# V4-AddOnLeer-V001.net
KiCad netlist of a schematic drawn in EAGLE
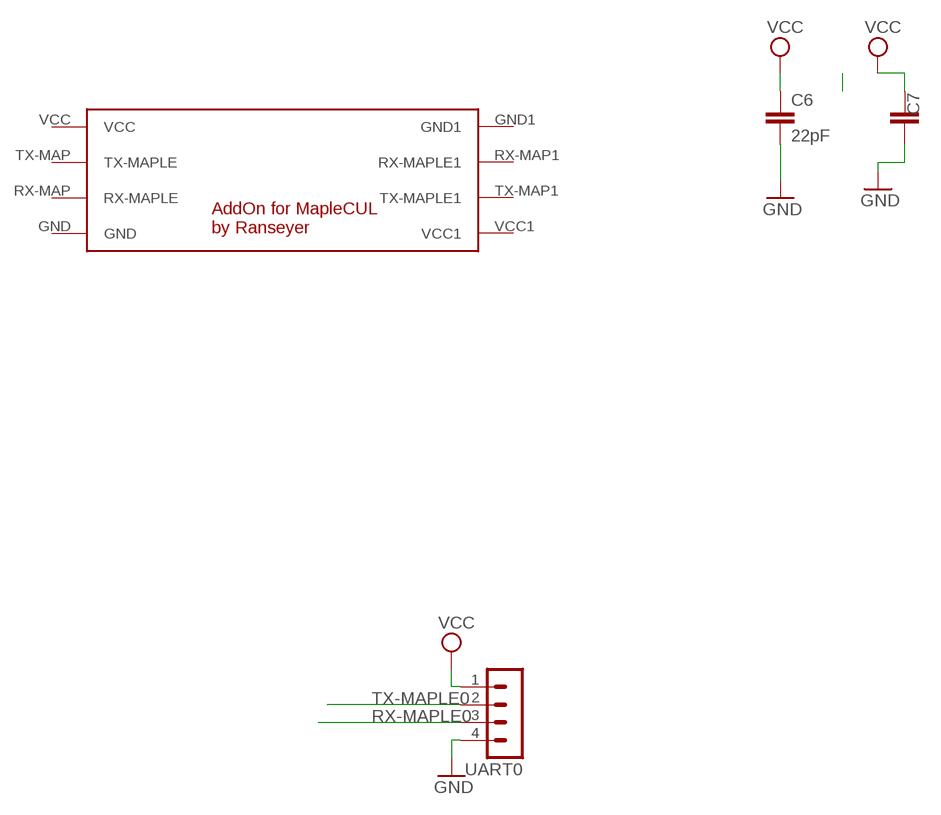
[diagram p0: schematic, sheet 1]

(export (version "E")
  (design (tool "Eeschema 10.0.6"))
  (components
    (comp (ref "C6")
      (value "22pF")
      (footprint "eagle-import:C0805")
      (libsource (lib "eagle-import") (part "C-EUC0805"))
    )
    (comp (ref "C7")
      (value "C-EUC1812")
      (footprint "eagle-import:C1812")
      (libsource (lib "eagle-import") (part "C-EUC1812"))
    )
    (comp (ref "U$1")
      (value "MAPLE-CUL-ADDON-V01")
      (footprint "eagle-import:MAPLE-CUL-V01")
      (libsource (lib "eagle-import") (part "MAPLE-CUL-ADDON-V01"))
    )
    (comp (ref "UART0")
      (value "MA04-1")
      (footprint "eagle-import:MA04-1")
      (libsource (lib "eagle-import") (part "MA04-1"))
    )
  )
  (nets
    (net (code "1") (name "/RX-MAPLE0") (class "Default")
      (node (ref "UART0") (pin "3") (pinfunction "3_3") (pintype "passive"))
    )
    (net (code "2") (name "/TX-MAPLE0") (class "Default")
      (node (ref "UART0") (pin "2") (pinfunction "2_2") (pintype "passive"))
    )
    (net (code "3") (name "GND") (class "Default")
      (node (ref "C6") (pin "2") (pinfunction "2_2") (pintype "passive"))
      (node (ref "C7") (pin "1") (pinfunction "1_1") (pintype "passive"))
      (node (ref "UART0") (pin "4") (pinfunction "4_4") (pintype "passive"))
    )
    (net (code "4") (name "VCC") (class "Default")
      (node (ref "C6") (pin "1") (pinfunction "1_1") (pintype "passive"))
      (node (ref "C7") (pin "2") (pinfunction "2_2") (pintype "passive"))
      (node (ref "UART0") (pin "1") (pinfunction "1_1") (pintype "passive"))
    )
    (net (code "5") (name "unconnected-(U$1-PadGND)") (class "Default")
      (node (ref "U$1") (pin "GND") (pinfunction "GND_GND") (pintype "bidirectional"))
    )
    (net (code "6") (name "unconnected-(U$1-PadGND1)") (class "Default")
      (node (ref "U$1") (pin "GND1") (pinfunction "GND1_GND1") (pintype "bidirectional"))
    )
    (net (code "7") (name "unconnected-(U$1-PadVCC)") (class "Default")
      (node (ref "U$1") (pin "VCC") (pinfunction "VCC_VCC") (pintype "bidirectional"))
    )
    (net (code "8") (name "unconnected-(U$1-PadVCC1)") (class "Default")
      (node (ref "U$1") (pin "VCC1") (pinfunction "VCC1_VCC1") (pintype "bidirectional"))
    )
    (net (code "9") (name "unconnected-(U$1-RX-MAPLE-PadRX-MAP)") (class "Default")
      (node (ref "U$1") (pin "RX-MAP") (pinfunction "RX-MAPLE_RX-MAP") (pintype "bidirectional"))
    )
    (net (code "10") (name "unconnected-(U$1-RX-MAPLE1-PadRX-MAP1)") (class "Default")
      (node (ref "U$1") (pin "RX-MAP1") (pinfunction "RX-MAPLE1_RX-MAP1") (pintype "bidirectional"))
    )
    (net (code "11") (name "unconnected-(U$1-TX-MAPLE-PadTX-MAP)") (class "Default")
      (node (ref "U$1") (pin "TX-MAP") (pinfunction "TX-MAPLE_TX-MAP") (pintype "bidirectional"))
    )
    (net (code "12") (name "unconnected-(U$1-TX-MAPLE1-PadTX-MAP1)") (class "Default")
      (node (ref "U$1") (pin "TX-MAP1") (pinfunction "TX-MAPLE1_TX-MAP1") (pintype "bidirectional"))
    )
  )
)
